# Buzzer.net
KiCad netlist of a schematic drawn in Altium Designer
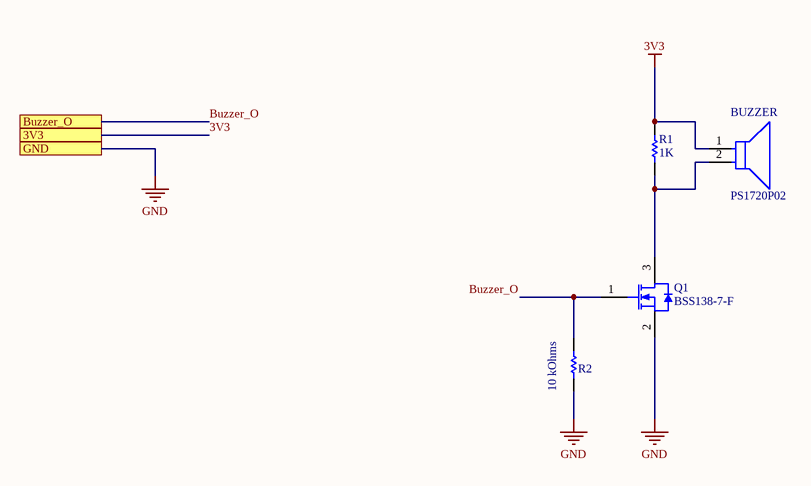
[diagram p0: Buzzer.SchDoc]

(export (version "E")
  (design (tool "Eeschema 10.0.6"))
  (components
    (comp (ref "BUZZER")
      (value "PS1720P02")
      (footprint "FP-PS1720P02-MFG")
      (description "AUDIO PIEZO TRANSDUCER 30V TH")
      (fields
        (field (name "OCTOPART") "https://octopart.com/ps1720p02-tdk-154429")
        (field (name "MANUFACTURER") "TDK Corporation")
      )
      (libsource (lib "Altium Content Vault") (part "5f581d31613f872430949aa526fd155"))
    )
    (comp (ref "Q1")
      (value "BSS138-7-F")
      (footprint "DIOD-SOT23-3_V")
      (description "N-Channel Enhancement Mode Mosfet, 50 V, 0.2 A, -55 to 150 degC, 3-Pin SOT23, RoHS, Tape and Reel")
      (fields (field (name "MANUFACTURER") "Diodes Inc"))
      (libsource (lib "Altium Content Vault") (part "NEMOS-GSD-3"))
    )
    (comp (ref "R1")
      (value "1K")
      (footprint "RESC0805(2012)_M")
      (description "1K 0.125W 1% 0805 (2012 Metric)  SMD")
      (fields (field (name "TOLERANCE") "1 %") (field (name "POWER") "0.125 W"))
      (libsource (lib "Altium Content Vault") (part "RES"))
    )
    (comp (ref "R2")
      (value "10 kOhms")
      (footprint "RESC2013X60X30ML20T20")
      (fields (field (name "PART NUMBER") "RK73B2ATTD103J") (field (name "MANUFACTURER") "KOA Speer"))
      (libsource (lib "Altium Content Vault") (part "RES"))
    )
  )
  (nets
    (net (code "1") (name "/Buzzer_O") (class "Default")
      (node (ref "Q1") (pin "1") (pinfunction "G_1") (pintype "passive"))
      (node (ref "R2") (pin "1") (pinfunction "1_1") (pintype "passive"))
    )
    (net (code "2") (name "3V3") (class "Default")
      (node (ref "BUZZER") (pin "1") (pinfunction "1_1") (pintype "passive"))
      (node (ref "R1") (pin "2") (pinfunction "2_2") (pintype "passive"))
    )
    (net (code "3") (name "GND") (class "Default")
      (node (ref "Q1") (pin "2") (pinfunction "S_2") (pintype "passive"))
      (node (ref "R2") (pin "2") (pinfunction "2_2") (pintype "passive"))
    )
    (net (code "4") (name "Net-(Q1-D)") (class "Default")
      (node (ref "BUZZER") (pin "2") (pinfunction "2_2") (pintype "passive"))
      (node (ref "Q1") (pin "3") (pinfunction "D_3") (pintype "passive"))
      (node (ref "R1") (pin "1") (pinfunction "1_1") (pintype "passive"))
    )
  )
)
